# rc.net
KiCad netlist of a schematic drawn in Altium Designer
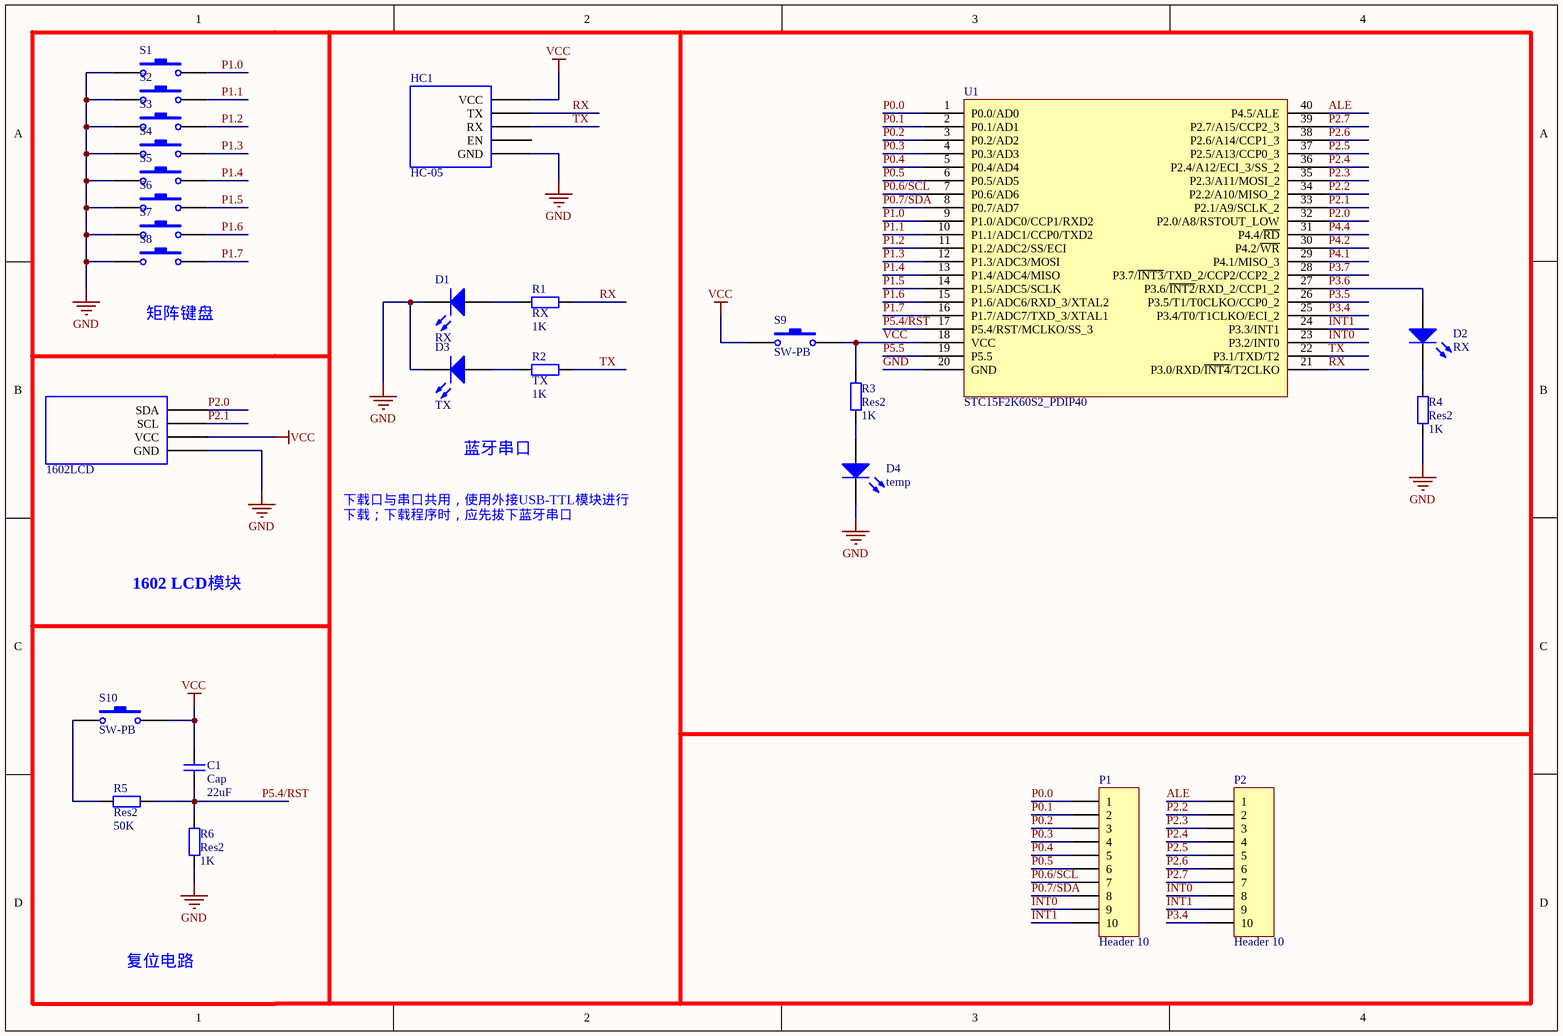
[diagram p0: rc.SchDoc]

(export (version "E")
  (design (tool "Eeschema 10.0.6"))
  (components
    (comp (ref "C1")
      (value "Cap")
      (footprint "RAD-0.3")
      (description "Capacitor")
      (fields (field (name "ALTIUM_VALUE") "22uF") (field (name "PUBLISHER") "Altium Limited"))
      (libsource (lib "Miscellaneous Devices") (part "Cap"))
    )
    (comp (ref "D1")
      (value "RX")
      (footprint "LED-0")
      (description "Typical INFRARED GaAs LED")
      (fields (field (name "PUBLISHER") "Altium Limited"))
      (libsource (lib "Miscellaneous Devices") (part "LED0"))
    )
    (comp (ref "D2")
      (value "RX")
      (footprint "LED-0")
      (description "Typical INFRARED GaAs LED")
      (fields (field (name "PUBLISHER") "Altium Limited"))
      (libsource (lib "Miscellaneous Devices") (part "LED0"))
    )
    (comp (ref "D3")
      (value "TX")
      (footprint "LED-0")
      (description "Typical INFRARED GaAs LED")
      (fields (field (name "PUBLISHER") "Altium Limited"))
      (libsource (lib "Miscellaneous Devices") (part "LED0"))
    )
    (comp (ref "D4")
      (value "temp")
      (footprint "LED-0")
      (description "Typical INFRARED GaAs LED")
      (fields (field (name "PUBLISHER") "Altium Limited"))
      (libsource (lib "Miscellaneous Devices") (part "LED0"))
    )
    (comp (ref "HC-1") (value "1602LCD") (libsource (lib "") (part "HC-05_1")))
    (comp (ref "HC1") (value "HC-05") (libsource (lib "hc05") (part "HC-05")))
    (comp (ref "P1")
      (value "Header 10")
      (footprint "HDR1X10")
      (description "Header, 10-Pin")
      (fields (field (name "PUBLISHER") "Altium Limited"))
      (libsource (lib "Miscellaneous Connectors") (part "Header 10"))
    )
    (comp (ref "P2")
      (value "Header 10")
      (footprint "HDR1X10")
      (description "Header, 10-Pin")
      (fields (field (name "PUBLISHER") "Altium Limited"))
      (libsource (lib "Miscellaneous Connectors") (part "Header 10"))
    )
    (comp (ref "R1")
      (value "RX")
      (footprint "AXIAL-0.4")
      (description "Resistor")
      (fields (field (name "ALTIUM_VALUE") "1K") (field (name "PUBLISHER") "Altium Limited"))
      (libsource (lib "Miscellaneous Devices") (part "Res2"))
    )
    (comp (ref "R2")
      (value "TX")
      (footprint "AXIAL-0.4")
      (description "Resistor")
      (fields (field (name "ALTIUM_VALUE") "1K") (field (name "PUBLISHER") "Altium Limited"))
      (libsource (lib "Miscellaneous Devices") (part "Res2"))
    )
    (comp (ref "R3")
      (value "Res2")
      (footprint "AXIAL-0.4")
      (description "Resistor")
      (fields (field (name "ALTIUM_VALUE") "1K") (field (name "PUBLISHER") "Altium Limited"))
      (libsource (lib "") (part "Res2_1"))
    )
    (comp (ref "R4")
      (value "Res2")
      (footprint "AXIAL-0.4")
      (description "Resistor")
      (fields (field (name "ALTIUM_VALUE") "1K") (field (name "PUBLISHER") "Altium Limited"))
      (libsource (lib "") (part "Res2_1"))
    )
    (comp (ref "R5")
      (value "Res2")
      (footprint "AXIAL-0.4")
      (description "Resistor")
      (fields (field (name "ALTIUM_VALUE") "50K") (field (name "PUBLISHER") "Altium Limited"))
      (libsource (lib "Miscellaneous Devices") (part "Res2"))
    )
    (comp (ref "R6")
      (value "Res2")
      (footprint "AXIAL-0.4")
      (description "Resistor")
      (fields (field (name "ALTIUM_VALUE") "1K") (field (name "PUBLISHER") "Altium Limited"))
      (libsource (lib "") (part "Res2_1"))
    )
    (comp (ref "S1")
      (value "SW-PB")
      (footprint "SPST-2")
      (description "Switch")
      (fields (field (name "PUBLISHER") "Altium Limited"))
      (libsource (lib "Miscellaneous Devices") (part "SW-PB"))
    )
    (comp (ref "S2")
      (value "SW-PB")
      (footprint "SPST-2")
      (description "Switch")
      (fields (field (name "PUBLISHER") "Altium Limited"))
      (libsource (lib "Miscellaneous Devices") (part "SW-PB"))
    )
    (comp (ref "S3")
      (value "SW-PB")
      (footprint "SPST-2")
      (description "Switch")
      (fields (field (name "PUBLISHER") "Altium Limited"))
      (libsource (lib "Miscellaneous Devices") (part "SW-PB"))
    )
    (comp (ref "S4")
      (value "SW-PB")
      (footprint "SPST-2")
      (description "Switch")
      (fields (field (name "PUBLISHER") "Altium Limited"))
      (libsource (lib "Miscellaneous Devices") (part "SW-PB"))
    )
    (comp (ref "S5")
      (value "SW-PB")
      (footprint "SPST-2")
      (description "Switch")
      (fields (field (name "PUBLISHER") "Altium Limited"))
      (libsource (lib "Miscellaneous Devices") (part "SW-PB"))
    )
    (comp (ref "S6")
      (value "SW-PB")
      (footprint "SPST-2")
      (description "Switch")
      (fields (field (name "PUBLISHER") "Altium Limited"))
      (libsource (lib "Miscellaneous Devices") (part "SW-PB"))
    )
    (comp (ref "S7")
      (value "SW-PB")
      (footprint "SPST-2")
      (description "Switch")
      (fields (field (name "PUBLISHER") "Altium Limited"))
      (libsource (lib "Miscellaneous Devices") (part "SW-PB"))
    )
    (comp (ref "S8")
      (value "SW-PB")
      (footprint "SPST-2")
      (description "Switch")
      (fields (field (name "PUBLISHER") "Altium Limited"))
      (libsource (lib "Miscellaneous Devices") (part "SW-PB"))
    )
    (comp (ref "S9")
      (value "SW-PB")
      (footprint "SPST-2")
      (description "Switch")
      (fields (field (name "PUBLISHER") "Altium Limited"))
      (libsource (lib "Miscellaneous Devices") (part "SW-PB"))
    )
    (comp (ref "S10")
      (value "SW-PB")
      (footprint "SPST-2")
      (description "Switch")
      (fields (field (name "PUBLISHER") "Altium Limited"))
      (libsource (lib "Miscellaneous Devices") (part "SW-PB"))
    )
    (comp (ref "U1")
      (value "STC15F2K60S2_PDIP40")
      (footprint "DIP40")
      (libsource (lib "stcmcu_altium_lib") (part "STC15F2K60S2_PDIP40"))
    )
  )
  (nets
    (net (code "1") (name "/ALE") (class "Default")
      (node (ref "P2") (pin "1") (pinfunction "1_1") (pintype "passive"))
      (node (ref "U1") (pin "40") (pinfunction "P4.5/ALE_40") (pintype "passive"))
    )
    (net (code "2") (name "/INT0") (class "Default")
      (node (ref "P1") (pin "9") (pinfunction "9_9") (pintype "passive"))
      (node (ref "P2") (pin "8") (pinfunction "8_8") (pintype "passive"))
      (node (ref "U1") (pin "23") (pinfunction "P3.2/INT0_23") (pintype "passive"))
    )
    (net (code "3") (name "/INT1") (class "Default")
      (node (ref "P1") (pin "10") (pinfunction "10_10") (pintype "passive"))
      (node (ref "P2") (pin "9") (pinfunction "9_9") (pintype "passive"))
      (node (ref "U1") (pin "24") (pinfunction "P3.3/INT1_24") (pintype "passive"))
    )
    (net (code "4") (name "/P0.0") (class "Default")
      (node (ref "P1") (pin "1") (pinfunction "1_1") (pintype "passive"))
      (node (ref "U1") (pin "1") (pinfunction "P0.0/AD0_1") (pintype "passive"))
    )
    (net (code "5") (name "/P0.1") (class "Default")
      (node (ref "P1") (pin "2") (pinfunction "2_2") (pintype "passive"))
      (node (ref "U1") (pin "2") (pinfunction "P0.1/AD1_2") (pintype "passive"))
    )
    (net (code "6") (name "/P0.2") (class "Default")
      (node (ref "P1") (pin "3") (pinfunction "3_3") (pintype "passive"))
      (node (ref "U1") (pin "3") (pinfunction "P0.2/AD2_3") (pintype "passive"))
    )
    (net (code "7") (name "/P0.3") (class "Default")
      (node (ref "P1") (pin "4") (pinfunction "4_4") (pintype "passive"))
      (node (ref "U1") (pin "4") (pinfunction "P0.3/AD3_4") (pintype "passive"))
    )
    (net (code "8") (name "/P0.4") (class "Default")
      (node (ref "P1") (pin "5") (pinfunction "5_5") (pintype "passive"))
      (node (ref "U1") (pin "5") (pinfunction "P0.4/AD4_5") (pintype "passive"))
    )
    (net (code "9") (name "/P0.5") (class "Default")
      (node (ref "P1") (pin "6") (pinfunction "6_6") (pintype "passive"))
      (node (ref "U1") (pin "6") (pinfunction "P0.5/AD5_6") (pintype "passive"))
    )
    (net (code "10") (name "/P0.6{slash}SCL") (class "Default")
      (node (ref "P1") (pin "7") (pinfunction "7_7") (pintype "passive"))
      (node (ref "U1") (pin "7") (pinfunction "P0.6/AD6_7") (pintype "passive"))
    )
    (net (code "11") (name "/P0.7{slash}SDA") (class "Default")
      (node (ref "P1") (pin "8") (pinfunction "8_8") (pintype "passive"))
      (node (ref "U1") (pin "8") (pinfunction "P0.7/AD7_8") (pintype "passive"))
    )
    (net (code "12") (name "/P1.0") (class "Default")
      (node (ref "S1") (pin "2") (pinfunction "2_2") (pintype "passive"))
      (node (ref "U1") (pin "9") (pinfunction "P1.0/ADC0/CCP1/RXD2_9") (pintype "passive"))
    )
    (net (code "13") (name "/P1.1") (class "Default")
      (node (ref "S2") (pin "2") (pinfunction "2_2") (pintype "passive"))
      (node (ref "U1") (pin "10") (pinfunction "P1.1/ADC1/CCP0/TXD2_10") (pintype "passive"))
    )
    (net (code "14") (name "/P1.2") (class "Default")
      (node (ref "S3") (pin "2") (pinfunction "2_2") (pintype "passive"))
      (node (ref "U1") (pin "11") (pinfunction "P1.2/ADC2/SS/ECI_11") (pintype "passive"))
    )
    (net (code "15") (name "/P1.3") (class "Default")
      (node (ref "S4") (pin "2") (pinfunction "2_2") (pintype "passive"))
      (node (ref "U1") (pin "12") (pinfunction "P1.3/ADC3/MOSI_12") (pintype "passive"))
    )
    (net (code "16") (name "/P1.4") (class "Default")
      (node (ref "S5") (pin "2") (pinfunction "2_2") (pintype "passive"))
      (node (ref "U1") (pin "13") (pinfunction "P1.4/ADC4/MISO_13") (pintype "passive"))
    )
    (net (code "17") (name "/P1.5") (class "Default")
      (node (ref "S6") (pin "2") (pinfunction "2_2") (pintype "passive"))
      (node (ref "U1") (pin "14") (pinfunction "P1.5/ADC5/SCLK_14") (pintype "passive"))
    )
    (net (code "18") (name "/P1.6") (class "Default")
      (node (ref "S7") (pin "2") (pinfunction "2_2") (pintype "passive"))
      (node (ref "U1") (pin "15") (pinfunction "P1.6/ADC6/RXD_3/XTAL2_15") (pintype "passive"))
    )
    (net (code "19") (name "/P1.7") (class "Default")
      (node (ref "S8") (pin "2") (pinfunction "2_2") (pintype "passive"))
      (node (ref "U1") (pin "16") (pinfunction "P1.7/ADC7/TXD_3/XTAL1_16") (pintype "passive"))
    )
    (net (code "20") (name "/P2.0") (class "Default")
      (node (ref "HC-1") (pin "25") (pinfunction "SDA_25") (pintype "passive"))
      (node (ref "U1") (pin "32") (pinfunction "P2.0/A8/RSTOUT_LOW_32") (pintype "passive"))
    )
    (net (code "21") (name "/P2.1") (class "Default")
      (node (ref "HC-1") (pin "26") (pinfunction "SCL_26") (pintype "passive"))
      (node (ref "U1") (pin "33") (pinfunction "P2.1/A9/SCLK_2_33") (pintype "passive"))
    )
    (net (code "22") (name "/P2.2") (class "Default")
      (node (ref "P2") (pin "2") (pinfunction "2_2") (pintype "passive"))
      (node (ref "U1") (pin "34") (pinfunction "P2.2/A10/MISO_2_34") (pintype "passive"))
    )
    (net (code "23") (name "/P2.3") (class "Default")
      (node (ref "P2") (pin "3") (pinfunction "3_3") (pintype "passive"))
      (node (ref "U1") (pin "35") (pinfunction "P2.3/A11/MOSI_2_35") (pintype "passive"))
    )
    (net (code "24") (name "/P2.4") (class "Default")
      (node (ref "P2") (pin "4") (pinfunction "4_4") (pintype "passive"))
      (node (ref "U1") (pin "36") (pinfunction "P2.4/A12/ECI_3/SS_2_36") (pintype "passive"))
    )
    (net (code "25") (name "/P2.5") (class "Default")
      (node (ref "P2") (pin "5") (pinfunction "5_5") (pintype "passive"))
      (node (ref "U1") (pin "37") (pinfunction "P2.5/A13/CCP0_3_37") (pintype "passive"))
    )
    (net (code "26") (name "/P2.6") (class "Default")
      (node (ref "P2") (pin "6") (pinfunction "6_6") (pintype "passive"))
      (node (ref "U1") (pin "38") (pinfunction "P2.6/A14/CCP1_3_38") (pintype "passive"))
    )
    (net (code "27") (name "/P2.7") (class "Default")
      (node (ref "P2") (pin "7") (pinfunction "7_7") (pintype "passive"))
      (node (ref "U1") (pin "39") (pinfunction "P2.7/A15/CCP2_3_39") (pintype "passive"))
    )
    (net (code "28") (name "/P3.4") (class "Default")
      (node (ref "P2") (pin "10") (pinfunction "10_10") (pintype "passive"))
      (node (ref "U1") (pin "25") (pinfunction "P3.4/T0/T1CLKO/ECI_2_25") (pintype "passive"))
    )
    (net (code "29") (name "/P3.5") (class "Default")
      (node (ref "U1") (pin "26") (pinfunction "P3.5/T1/T0CLKO/CCP0_2_26") (pintype "passive"))
    )
    (net (code "30") (name "/P3.6") (class "Default")
      (node (ref "D2") (pin "1") (pinfunction "A_1") (pintype "passive"))
      (node (ref "U1") (pin "27") (pinfunction "P3.6/~{INT2}/RXD_2/CCP1_2_27") (pintype "passive"))
    )
    (net (code "31") (name "/P3.7") (class "Default")
      (node (ref "U1") (pin "28") (pinfunction "P3.7/~{INT3}/TXD_2/CCP2/CCP2_2_28") (pintype "passive"))
    )
    (net (code "32") (name "/P4.1") (class "Default")
      (node (ref "U1") (pin "29") (pinfunction "P4.1/MISO_3_29") (pintype "passive"))
    )
    (net (code "33") (name "/P4.2") (class "Default")
      (node (ref "U1") (pin "30") (pinfunction "P4.2/~{WR}_30") (pintype "passive"))
    )
    (net (code "34") (name "/P4.4") (class "Default")
      (node (ref "U1") (pin "31") (pinfunction "P4.4/~{RD}_31") (pintype "passive"))
    )
    (net (code "35") (name "/P5.4{slash}RST") (class "Default")
      (node (ref "C1") (pin "1") (pinfunction "1_1") (pintype "passive"))
      (node (ref "R5") (pin "2") (pinfunction "2_2") (pintype "passive"))
      (node (ref "R6") (pin "2") (pinfunction "2_2") (pintype "passive"))
      (node (ref "U1") (pin "17") (pinfunction "P5.4/RST/MCLKO/SS_3_17") (pintype "passive"))
    )
    (net (code "36") (name "/P5.5") (class "Default")
      (node (ref "U1") (pin "19") (pinfunction "P5.5_19") (pintype "passive"))
    )
    (net (code "37") (name "/RX") (class "Default")
      (node (ref "HC1") (pin "34") (pinfunction "TX_34") (pintype "passive"))
      (node (ref "R1") (pin "2") (pinfunction "2_2") (pintype "passive"))
      (node (ref "U1") (pin "21") (pinfunction "P3.0/RXD/~{INT4}/T2CLKO_21") (pintype "passive"))
    )
    (net (code "38") (name "/TX") (class "Default")
      (node (ref "HC1") (pin "35") (pinfunction "RX_35") (pintype "passive"))
      (node (ref "R2") (pin "2") (pinfunction "2_2") (pintype "passive"))
      (node (ref "U1") (pin "22") (pinfunction "P3.1/TXD/T2_22") (pintype "passive"))
    )
    (net (code "39") (name "GND") (class "Default")
      (node (ref "D1") (pin "2") (pinfunction "K_2") (pintype "passive"))
      (node (ref "D3") (pin "2") (pinfunction "K_2") (pintype "passive"))
      (node (ref "D4") (pin "2") (pinfunction "K_2") (pintype "passive"))
      (node (ref "HC-1") (pin "28") (pinfunction "GND_28") (pintype "passive"))
      (node (ref "HC1") (pin "37") (pinfunction "GND_37") (pintype "passive"))
      (node (ref "R4") (pin "1") (pinfunction "1_1") (pintype "passive"))
      (node (ref "R6") (pin "1") (pinfunction "1_1") (pintype "passive"))
      (node (ref "S1") (pin "1") (pinfunction "1_1") (pintype "passive"))
      (node (ref "S2") (pin "1") (pinfunction "1_1") (pintype "passive"))
      (node (ref "S3") (pin "1") (pinfunction "1_1") (pintype "passive"))
      (node (ref "S4") (pin "1") (pinfunction "1_1") (pintype "passive"))
      (node (ref "S5") (pin "1") (pinfunction "1_1") (pintype "passive"))
      (node (ref "S6") (pin "1") (pinfunction "1_1") (pintype "passive"))
      (node (ref "S7") (pin "1") (pinfunction "1_1") (pintype "passive"))
      (node (ref "S8") (pin "1") (pinfunction "1_1") (pintype "passive"))
      (node (ref "U1") (pin "20") (pinfunction "GND_20") (pintype "passive"))
    )
    (net (code "40") (name "Net-(D1-A)") (class "Default")
      (node (ref "D1") (pin "1") (pinfunction "A_1") (pintype "passive"))
      (node (ref "R1") (pin "1") (pinfunction "1_1") (pintype "passive"))
    )
    (net (code "41") (name "Net-(D2-K)") (class "Default")
      (node (ref "D2") (pin "2") (pinfunction "K_2") (pintype "passive"))
      (node (ref "R4") (pin "2") (pinfunction "2_2") (pintype "passive"))
    )
    (net (code "42") (name "Net-(D3-A)") (class "Default")
      (node (ref "D3") (pin "1") (pinfunction "A_1") (pintype "passive"))
      (node (ref "R2") (pin "1") (pinfunction "1_1") (pintype "passive"))
    )
    (net (code "43") (name "Net-(D4-A)") (class "Default")
      (node (ref "D4") (pin "1") (pinfunction "A_1") (pintype "passive"))
      (node (ref "R3") (pin "1") (pinfunction "1_1") (pintype "passive"))
    )
    (net (code "44") (name "Net-(R5-Pad1)") (class "Default")
      (node (ref "R5") (pin "1") (pinfunction "1_1") (pintype "passive"))
      (node (ref "S10") (pin "1") (pinfunction "1_1") (pintype "passive"))
    )
    (net (code "45") (name "VCC") (class "Default")
      (node (ref "C1") (pin "2") (pinfunction "2_2") (pintype "passive"))
      (node (ref "HC-1") (pin "27") (pinfunction "VCC_27") (pintype "passive"))
      (node (ref "HC1") (pin "33") (pinfunction "VCC_33") (pintype "passive"))
      (node (ref "R3") (pin "2") (pinfunction "2_2") (pintype "passive"))
      (node (ref "S10") (pin "2") (pinfunction "2_2") (pintype "passive"))
      (node (ref "S9") (pin "1") (pinfunction "1_1") (pintype "passive"))
      (node (ref "S9") (pin "2") (pinfunction "2_2") (pintype "passive"))
      (node (ref "U1") (pin "18") (pinfunction "VCC_18") (pintype "passive"))
    )
    (net (code "46") (name "unconnected-(HC1-EN-Pad36)") (class "Default")
      (node (ref "HC1") (pin "36") (pinfunction "EN_36") (pintype "passive"))
    )
  )
)
